# Plugv1.net
KiCad netlist of a schematic drawn in EAGLE
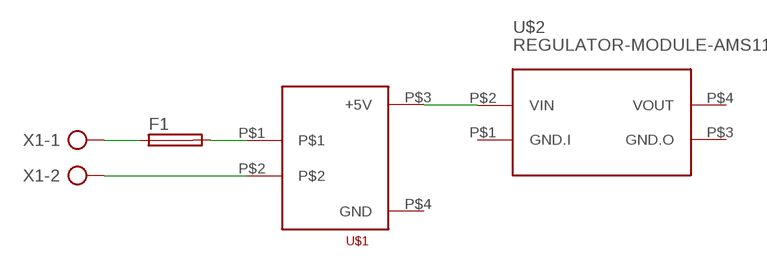
[diagram p0: schematic, sheet 1]

(export (version "E")
  (design (tool "Eeschema 10.0.6"))
  (components
    (comp (ref "F1")
      (value "SH22,5A")
      (footprint "eagle-import:SH22,5A")
      (fields (field (name "MPN") "0031.7701.11"))
      (libsource (lib "eagle-import") (part "SH22,5A"))
    )
    (comp (ref "U$1")
      (value "HLK-PM01")
      (footprint "eagle-import:HLK-PM01")
      (libsource (lib "eagle-import") (part "HLK-PM01"))
    )
    (comp (ref "U$2")
      (value "REGULATOR-MODULE-AMS1117")
      (footprint "eagle-import:REGULATOR-MODULE-AMS1117")
      (libsource (lib "eagle-import") (part "REGULATOR-MODULE-AMS1117"))
    )
    (comp (ref "X1")
      (value "AK500/2-H")
      (footprint "eagle-import:AK500_2-H")
      (libsource (lib "eagle-import") (part "AK500/2-H"))
    )
  )
  (nets
    (net (code "1") (name "Net-(F1-Pad2)") (class "Default")
      (node (ref "F1") (pin "2") (pinfunction "2_2") (pintype "passive"))
      (node (ref "U$1") (pin "P$1") (pinfunction "P$1_P$1") (pintype "bidirectional"))
    )
    (net (code "2") (name "Net-(X1A-KL)") (class "Default")
      (node (ref "F1") (pin "1") (pinfunction "1_1") (pintype "passive"))
      (node (ref "X1") (pin "1") (pinfunction "KL_1") (pintype "passive"))
    )
    (net (code "3") (name "Net-(X1B-KL)") (class "Default")
      (node (ref "U$1") (pin "P$2") (pinfunction "P$2_P$2") (pintype "bidirectional"))
      (node (ref "X1") (pin "2") (pinfunction "KL_2") (pintype "passive"))
    )
    (net (code "4") (name "unconnected-(U$1-+5V-PadP$3)") (class "Default")
      (node (ref "U$1") (pin "P$3") (pinfunction "+5V_P$3") (pintype "bidirectional"))
    )
    (net (code "5") (name "unconnected-(U$1-GND-PadP$4)") (class "Default")
      (node (ref "U$1") (pin "P$4") (pinfunction "GND_P$4") (pintype "bidirectional"))
    )
    (net (code "6") (name "unconnected-(U$2-GND.I-PadP$1)") (class "Default")
      (node (ref "U$2") (pin "P$1") (pinfunction "GND.I_P$1") (pintype "bidirectional"))
    )
    (net (code "7") (name "unconnected-(U$2-GND.O-PadP$3)") (class "Default")
      (node (ref "U$2") (pin "P$3") (pinfunction "GND.O_P$3") (pintype "bidirectional"))
    )
    (net (code "8") (name "unconnected-(U$2-VIN-PadP$2)") (class "Default")
      (node (ref "U$2") (pin "P$2") (pinfunction "VIN_P$2") (pintype "bidirectional"))
    )
    (net (code "9") (name "unconnected-(U$2-VOUT-PadP$4)") (class "Default")
      (node (ref "U$2") (pin "P$4") (pinfunction "VOUT_P$4") (pintype "bidirectional"))
    )
  )
)
